# ControllaBLE-Dual-SNES-v01.net
KiCad netlist of a schematic drawn in EAGLE
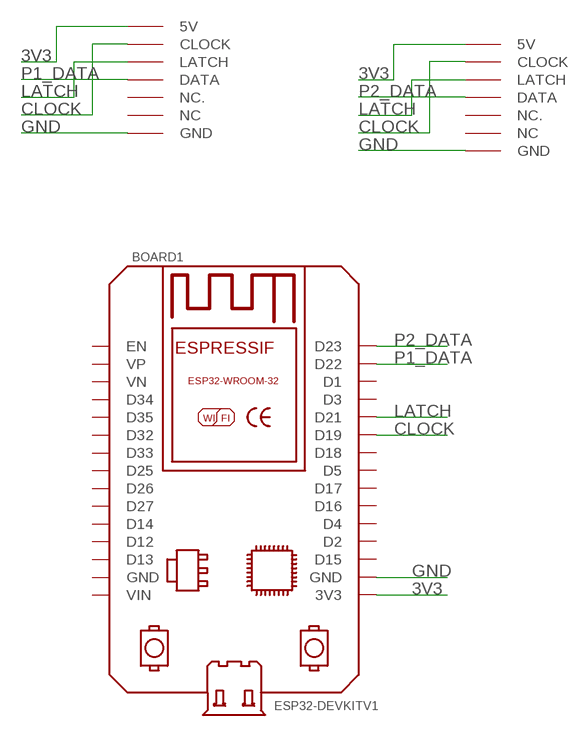
[diagram p0: schematic, sheet 1]

(export (version "E")
  (design (tool "Eeschema 10.0.6"))
  (components
    (comp (ref "BOARD1")
      (value "ESP32DEVKITV1")
      (footprint "eagle-import:ESP32-DEVKITV1")
      (libsource (lib "eagle-import") (part "ESP32DEVKITV1"))
    )
    (comp (ref "U$1")
      (value "SNESCONN")
      (footprint "eagle-import:SNESCONN")
      (libsource (lib "eagle-import") (part "SNESCONN"))
    )
    (comp (ref "U$2")
      (value "SNESCONN")
      (footprint "eagle-import:SNESCONN")
      (libsource (lib "eagle-import") (part "SNESCONN"))
    )
  )
  (nets
    (net (code "1") (name "/3V3") (class "Default")
      (node (ref "BOARD1") (pin "3V3") (pinfunction "3V3_3V3") (pintype "bidirectional"))
      (node (ref "U$1") (pin "5V") (pinfunction "5V_5V") (pintype "input"))
      (node (ref "U$2") (pin "5V") (pinfunction "5V_5V") (pintype "input"))
    )
    (net (code "2") (name "/CLOCK") (class "Default")
      (node (ref "BOARD1") (pin "D19") (pinfunction "D19_D19") (pintype "bidirectional"))
      (node (ref "U$1") (pin "CLOCK") (pinfunction "CLOCK_CLOCK") (pintype "input"))
      (node (ref "U$2") (pin "CLOCK") (pinfunction "CLOCK_CLOCK") (pintype "input"))
    )
    (net (code "3") (name "/GND") (class "Default")
      (node (ref "BOARD1") (pin "GND@1") (pinfunction "GND_GND@1") (pintype "bidirectional"))
      (node (ref "U$1") (pin "GND") (pinfunction "GND_GND") (pintype "power_in"))
      (node (ref "U$2") (pin "GND") (pinfunction "GND_GND") (pintype "power_in"))
    )
    (net (code "4") (name "/LATCH") (class "Default")
      (node (ref "BOARD1") (pin "D21") (pinfunction "D21_D21") (pintype "bidirectional"))
      (node (ref "U$1") (pin "LATCH") (pinfunction "LATCH_LATCH") (pintype "input"))
      (node (ref "U$2") (pin "LATCH") (pinfunction "LATCH_LATCH") (pintype "input"))
    )
    (net (code "5") (name "/P1_DATA") (class "Default")
      (node (ref "BOARD1") (pin "D22") (pinfunction "D22_D22") (pintype "bidirectional"))
      (node (ref "U$1") (pin "DATA") (pinfunction "DATA_DATA") (pintype "bidirectional"))
    )
    (net (code "6") (name "/P2_DATA") (class "Default")
      (node (ref "BOARD1") (pin "D23") (pinfunction "D23_D23") (pintype "bidirectional"))
      (node (ref "U$2") (pin "DATA") (pinfunction "DATA_DATA") (pintype "bidirectional"))
    )
    (net (code "7") (name "unconnected-(BOARD1-PadD1)") (class "Default")
      (node (ref "BOARD1") (pin "D1") (pinfunction "D1_D1") (pintype "bidirectional"))
    )
    (net (code "8") (name "unconnected-(BOARD1-PadD2)") (class "Default")
      (node (ref "BOARD1") (pin "D2") (pinfunction "D2_D2") (pintype "bidirectional"))
    )
    (net (code "9") (name "unconnected-(BOARD1-PadD3)") (class "Default")
      (node (ref "BOARD1") (pin "D3") (pinfunction "D3_D3") (pintype "bidirectional"))
    )
    (net (code "10") (name "unconnected-(BOARD1-PadD4)") (class "Default")
      (node (ref "BOARD1") (pin "D4") (pinfunction "D4_D4") (pintype "bidirectional"))
    )
    (net (code "11") (name "unconnected-(BOARD1-PadD5)") (class "Default")
      (node (ref "BOARD1") (pin "D5") (pinfunction "D5_D5") (pintype "bidirectional"))
    )
    (net (code "12") (name "unconnected-(BOARD1-PadD12)") (class "Default")
      (node (ref "BOARD1") (pin "D12") (pinfunction "D12_D12") (pintype "bidirectional"))
    )
    (net (code "13") (name "unconnected-(BOARD1-PadD13)") (class "Default")
      (node (ref "BOARD1") (pin "D13") (pinfunction "D13_D13") (pintype "bidirectional"))
    )
    (net (code "14") (name "unconnected-(BOARD1-PadD14)") (class "Default")
      (node (ref "BOARD1") (pin "D14") (pinfunction "D14_D14") (pintype "bidirectional"))
    )
    (net (code "15") (name "unconnected-(BOARD1-PadD15)") (class "Default")
      (node (ref "BOARD1") (pin "D15") (pinfunction "D15_D15") (pintype "bidirectional"))
    )
    (net (code "16") (name "unconnected-(BOARD1-PadD16)") (class "Default")
      (node (ref "BOARD1") (pin "D16") (pinfunction "D16_D16") (pintype "bidirectional"))
    )
    (net (code "17") (name "unconnected-(BOARD1-PadD17)") (class "Default")
      (node (ref "BOARD1") (pin "D17") (pinfunction "D17_D17") (pintype "bidirectional"))
    )
    (net (code "18") (name "unconnected-(BOARD1-PadD18)") (class "Default")
      (node (ref "BOARD1") (pin "D18") (pinfunction "D18_D18") (pintype "bidirectional"))
    )
    (net (code "19") (name "unconnected-(BOARD1-PadD25)") (class "Default")
      (node (ref "BOARD1") (pin "D25") (pinfunction "D25_D25") (pintype "bidirectional"))
    )
    (net (code "20") (name "unconnected-(BOARD1-PadD26)") (class "Default")
      (node (ref "BOARD1") (pin "D26") (pinfunction "D26_D26") (pintype "bidirectional"))
    )
    (net (code "21") (name "unconnected-(BOARD1-PadD27)") (class "Default")
      (node (ref "BOARD1") (pin "D27") (pinfunction "D27_D27") (pintype "bidirectional"))
    )
    (net (code "22") (name "unconnected-(BOARD1-PadD32)") (class "Default")
      (node (ref "BOARD1") (pin "D32") (pinfunction "D32_D32") (pintype "bidirectional"))
    )
    (net (code "23") (name "unconnected-(BOARD1-PadD33)") (class "Default")
      (node (ref "BOARD1") (pin "D33") (pinfunction "D33_D33") (pintype "bidirectional"))
    )
    (net (code "24") (name "unconnected-(BOARD1-PadD34)") (class "Default")
      (node (ref "BOARD1") (pin "D34") (pinfunction "D34_D34") (pintype "bidirectional"))
    )
    (net (code "25") (name "unconnected-(BOARD1-PadD35)") (class "Default")
      (node (ref "BOARD1") (pin "D35") (pinfunction "D35_D35") (pintype "bidirectional"))
    )
    (net (code "26") (name "unconnected-(BOARD1-PadEN)") (class "Default")
      (node (ref "BOARD1") (pin "EN") (pinfunction "EN_EN") (pintype "bidirectional"))
    )
    (net (code "27") (name "unconnected-(BOARD1-PadGND)") (class "Default")
      (node (ref "BOARD1") (pin "GND") (pinfunction "GND_GND") (pintype "bidirectional"))
    )
    (net (code "28") (name "unconnected-(BOARD1-PadVIN)") (class "Default")
      (node (ref "BOARD1") (pin "VIN") (pinfunction "VIN_VIN") (pintype "bidirectional"))
    )
    (net (code "29") (name "unconnected-(BOARD1-PadVN)") (class "Default")
      (node (ref "BOARD1") (pin "VN") (pinfunction "VN_VN") (pintype "bidirectional"))
    )
    (net (code "30") (name "unconnected-(BOARD1-PadVP)") (class "Default")
      (node (ref "BOARD1") (pin "VP") (pinfunction "VP_VP") (pintype "bidirectional"))
    )
    (net (code "31") (name "unconnected-(U$1-PadNC)") (class "Default")
      (node (ref "U$1") (pin "NC") (pinfunction "NC_NC") (pintype "no_connect"))
    )
    (net (code "32") (name "unconnected-(U$1-PadNC.)") (class "Default")
      (node (ref "U$1") (pin "NC.") (pinfunction "NC._NC.") (pintype "no_connect"))
    )
    (net (code "33") (name "unconnected-(U$2-PadNC)") (class "Default")
      (node (ref "U$2") (pin "NC") (pinfunction "NC_NC") (pintype "no_connect"))
    )
    (net (code "34") (name "unconnected-(U$2-PadNC.)") (class "Default")
      (node (ref "U$2") (pin "NC.") (pinfunction "NC._NC.") (pintype "no_connect"))
    )
  )
)
